# 03_-CONNECTOR_SBC.net
KiCad netlist of a schematic drawn in Altium Designer
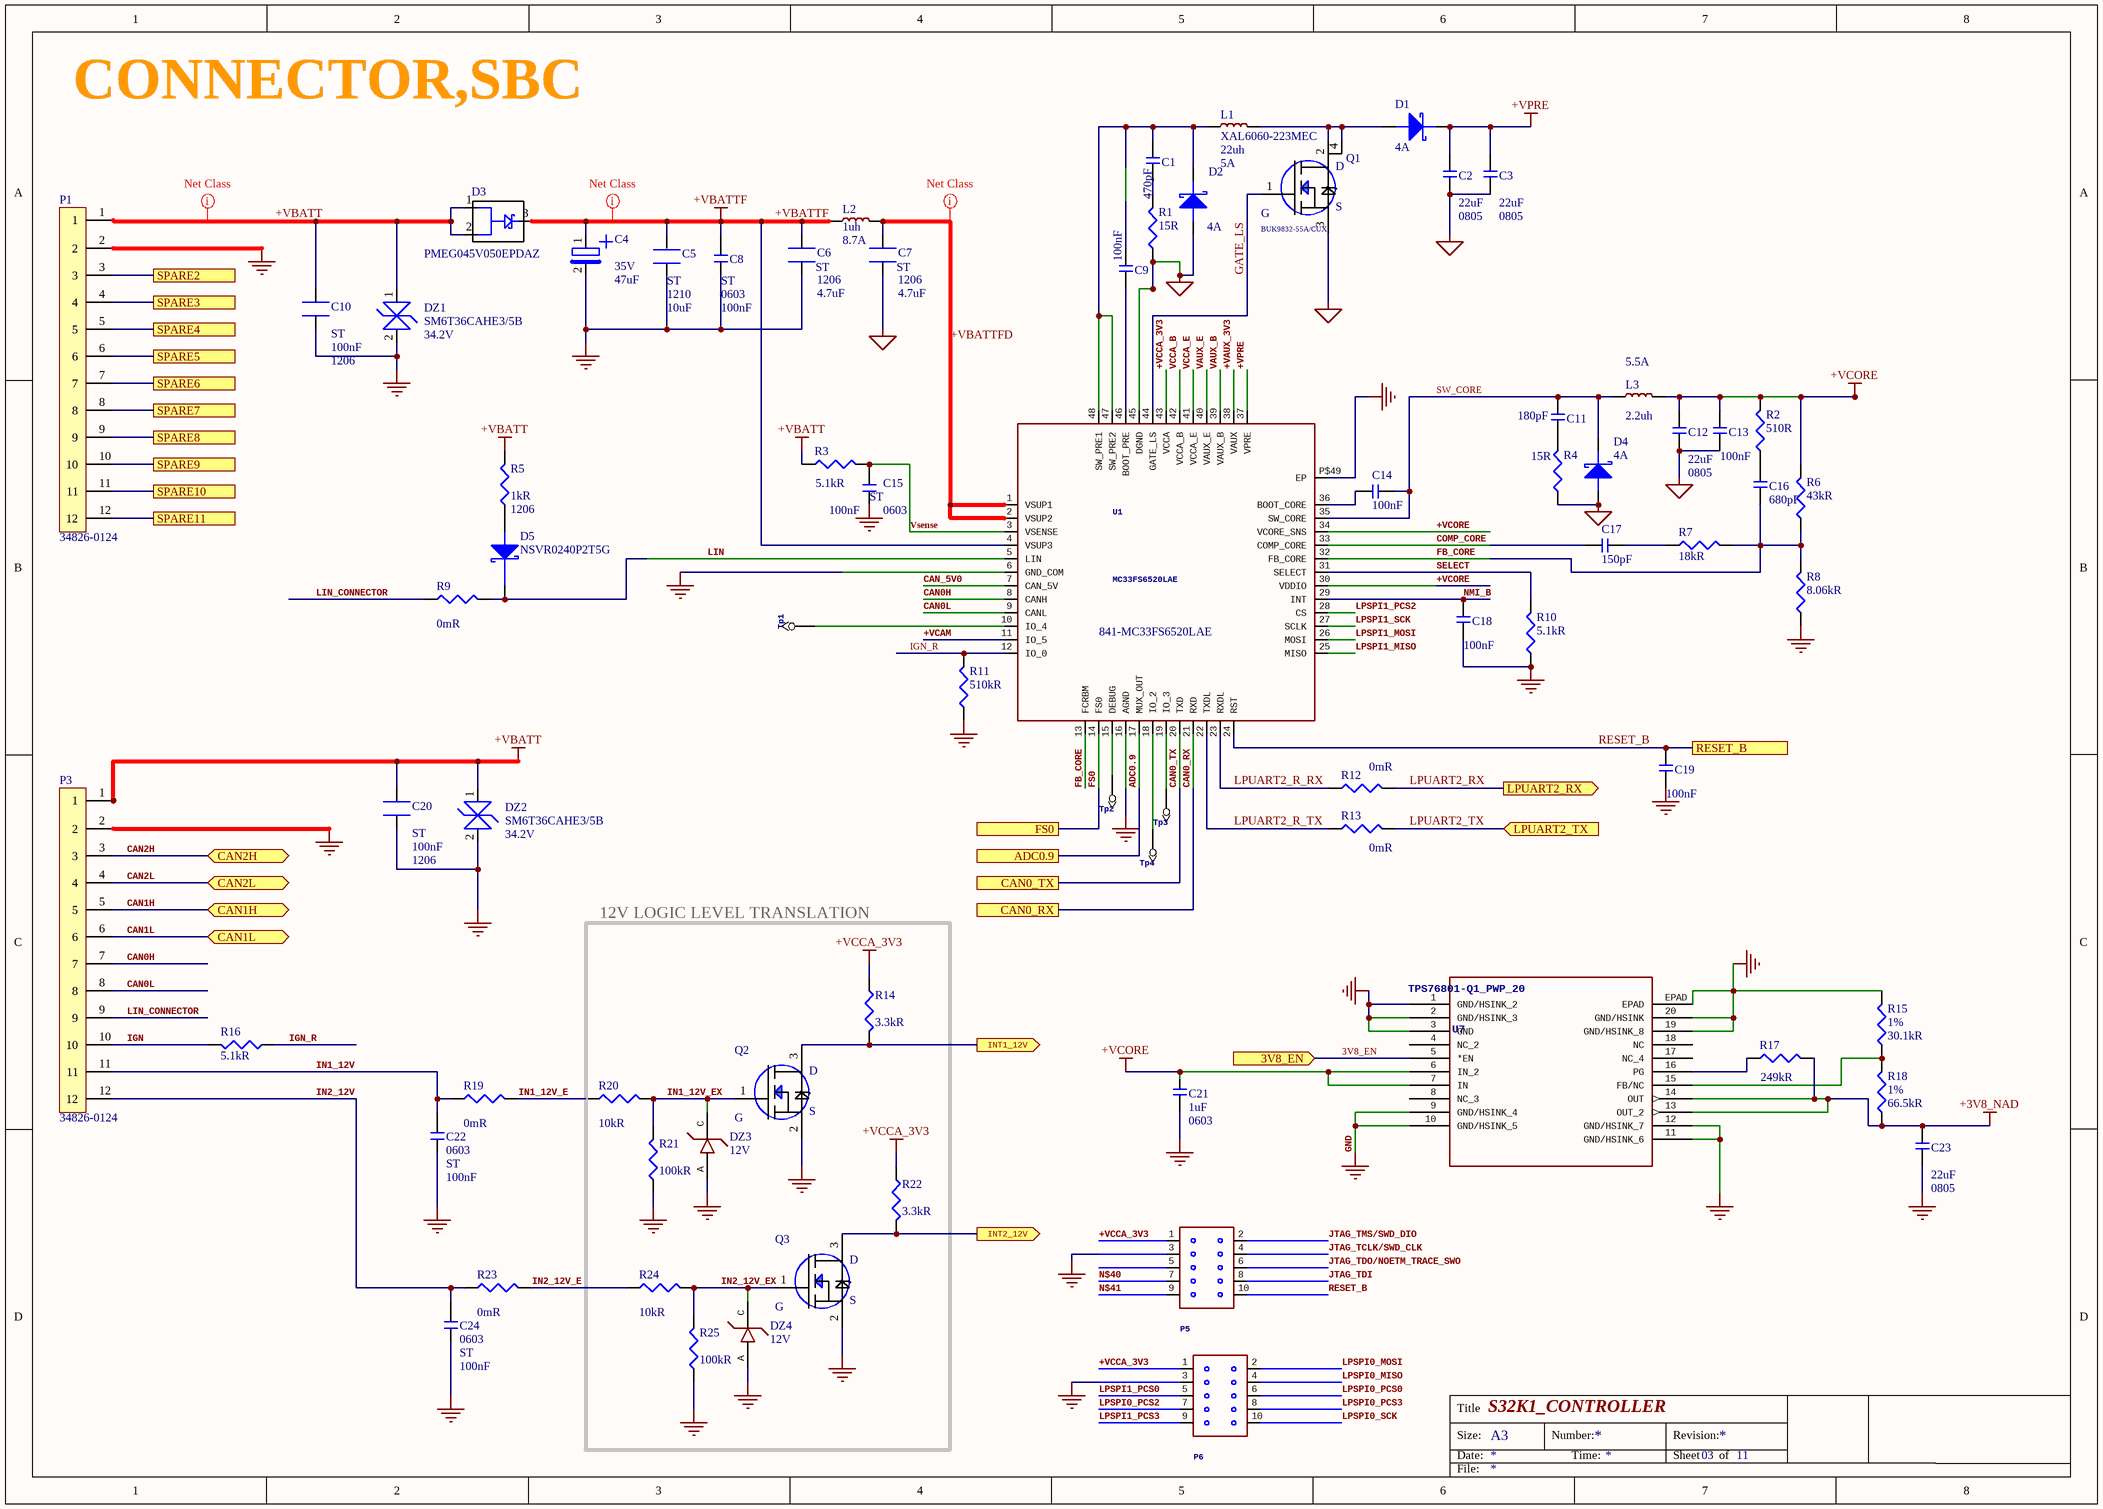
[diagram p0: [03]-CONNECTOR,SBC.SchDoc]

(export (version "E")
  (design (tool "Eeschema 10.0.6"))
  (components
    (comp (ref "C1")
      (value "C0402S471K3RACAUTO")
      (footprint "CAP0402")
      (description "Cap Ceramic 470pF 25V X7R 10% SMD 0402 125°C Paper T/R")
      (fields (field (name "MANUFACTURER") "KEMET") (field (name "PARAMETER 1") "470pF"))
      (libsource (lib "altium-import") (part "root_0_C0402S471K3RACAUTO_"))
    )
    (comp (ref "C2")
      (value "GRT21BR61E226ME13L")
      (footprint "CAP0805")
      (description "0805 22 uF 25 V ±20% Tolerance X5R Multilayer Ceramic Capacitor")
      (fields
        (field (name "MANUFACTURER") "Murata")
        (field (name "TOLERANCE") "20%")
        (field (name "CAPACITANCE") "22uF")
        (field (name "CASE/PACKAGE") "0805")
      )
      (libsource (lib "altium-import") (part "root_0_GRT21BR61E226ME13L_"))
    )
    (comp (ref "C3")
      (value "GRT21BR61E226ME13L")
      (footprint "CAP0805")
      (description "0805 22 uF 25 V ±20% Tolerance X5R Multilayer Ceramic Capacitor")
      (fields
        (field (name "MANUFACTURER") "Murata")
        (field (name "TOLERANCE") "20%")
        (field (name "CAPACITANCE") "22uF")
        (field (name "CASE/PACKAGE") "0805")
      )
      (libsource (lib "altium-import") (part "root_0_GRT21BR61E226ME13L_"))
    )
    (comp (ref "C4")
      (value "EMZA350ADA470MF61G")
      (footprint "CAPAE7263X58L")
      (description "Aluminum Electrolytic Capacitor 47UF 35V 20%, SMD, Full Reel")
      (fields
        (field (name "MANUFACTURER") "United Chemi-Con")
        (field (name "TOLERANCE") "20%")
        (field (name "VOLTAGE RATING") "35V")
        (field (name "CAPACITANCE") "47uF")
      )
      (libsource (lib "altium-import") (part "root_0_EMZA350ADA470MF61G_"))
    )
    (comp (ref "C5")
      (value "CGA6P3X7S1H106K250AE")
      (description "Cap Ceramic 10uF 50V X7S 10% Pad SMD 1210 Soft Termination 125C Automotive T/R")
      (fields
        (field (name "MANUFACTURER") "TDK")
        (field (name "TOLERANCE") "10%")
        (field (name "PARAMETER 1") "ST")
        (field (name "CASE CODE (IMPERIAL)") "1210")
        (field (name "CAPACITANCE") "10uF")
      )
      (libsource (lib "altium-import") (part "root_0_CGA6P3X7S1H106K250AE_"))
    )
    (comp (ref "C6")
      (value "CGA5L3X7R1H475K160AE")
      (footprint "CAP1206")
      (description "Cap Ceramic 4.7uF 50V X7R 10% Pad SMD 1206 Soft Termination 125C Automotive T/R")
      (fields
        (field (name "MANUFACTURER") "TDK")
        (field (name "TOLERANCE") "10%")
        (field (name "CASE CODE (IMPERIAL)") "1206")
        (field (name "CAPACITANCE") "4.7uF")
        (field (name "PARAMETER 1") "ST")
      )
      (libsource (lib "altium-import") (part "root_0_CGA5L3X7R1H475K160AE_"))
    )
    (comp (ref "C7")
      (value "CGA5L3X7R1H475K160AE")
      (footprint "CAP1206")
      (description "Cap Ceramic 4.7uF 50V X7R 10% Pad SMD 1206 Soft Termination 125C Automotive T/R")
      (fields
        (field (name "MANUFACTURER") "TDK")
        (field (name "TOLERANCE") "10%")
        (field (name "CASE CODE (IMPERIAL)") "1206")
        (field (name "CAPACITANCE") "4.7uF")
        (field (name "PARAMETER 1") "ST")
      )
      (libsource (lib "altium-import") (part "root_0_CGA5L3X7R1H475K160AE_"))
    )
    (comp (ref "C8")
      (value "06035C104K4Z2A")
      (footprint "CAP0603")
      (description "Capacitor: ceramic; MLCC; 100nF; 50V; X7R; ±10%; SMD; 0603")
      (fields
        (field (name "MANUFACTURER") "AVX")
        (field (name "TOLERANCE") "10%")
        (field (name "CASE CODE (IMPERIAL)") "0603")
        (field (name "PARAMETER 1") "ST")
        (field (name "CAPACITANCE") "100nF")
      )
      (libsource (lib "WeOnReferenceBoard") (part "06035C104K4Z2A"))
    )
    (comp (ref "C9")
      (value "GCM155R71C104KA55D")
      (footprint "CAP0402")
      (description "Multilayer Ceramic Capacitors (MLCC) - SMD/SMT 0402 0.1uF 16volts X7R 10%")
      (fields
        (field (name "MANUFACTURER") "Murata")
        (field (name "TOLERANCE") "10%")
        (field (name "CAPACITANCE") "100nF")
      )
      (libsource (lib "altium-import") (part "root_0_GCM155R71C104KA55D_"))
    )
    (comp (ref "C10")
      (value "C1206X104K2RACAUTO")
      (footprint "CAP1206")
      (description "Cap Ceramic 0.1uF 200V X7R 10% Pad SMD 1206 Flexible Termination 125C Automotive Medical T/R")
      (fields
        (field (name "MANUFACTURER") "KEMET")
        (field (name "TOLERANCE") "10%")
        (field (name "PARAMETER 1") "ST")
        (field (name "CAPACITANCE") "100nF")
        (field (name "CASE/PACKAGE") "1206")
      )
      (libsource (lib "WeOnReferenceSchlib") (part "C1206X104K2RACAUTO"))
    )
    (comp (ref "C11")
      (value "UMK105CH181JVHF")
      (footprint "CAP0402")
      (description "Cap Ceramic 180pF 50V 0402")
      (fields (field (name "MANUFACTURER") "Taiyo Yuden") (field (name "PARAMETER 1") "180pF"))
      (libsource (lib "altium-import") (part "root_0_UMK105CH181JVHF_"))
    )
    (comp (ref "C12")
      (value "GRT21BR61E226ME13L")
      (footprint "CAP0805")
      (description "0805 22 uF 25 V ±20% Tolerance X5R Multilayer Ceramic Capacitor")
      (fields
        (field (name "MANUFACTURER") "Murata")
        (field (name "TOLERANCE") "20%")
        (field (name "CAPACITANCE") "22uF")
        (field (name "CASE/PACKAGE") "0805")
      )
      (libsource (lib "altium-import") (part "root_0_GRT21BR61E226ME13L_"))
    )
    (comp (ref "C13")
      (value "GCM155R71C104KA55D")
      (footprint "CAP0402")
      (description "Multilayer Ceramic Capacitors (MLCC) - SMD/SMT 0402 0.1uF 16volts X7R 10%")
      (fields
        (field (name "MANUFACTURER") "Murata")
        (field (name "TOLERANCE") "10%")
        (field (name "CAPACITANCE") "100nF")
      )
      (libsource (lib "altium-import") (part "root_0_GCM155R71C104KA55D_"))
    )
    (comp (ref "C14")
      (value "GCM155R71C104KA55D")
      (footprint "CAP0402")
      (description "Multilayer Ceramic Capacitors (MLCC) - SMD/SMT 0402 0.1uF 16volts X7R 10%")
      (fields
        (field (name "MANUFACTURER") "Murata")
        (field (name "TOLERANCE") "10%")
        (field (name "CAPACITANCE") "100nF")
      )
      (libsource (lib "altium-import") (part "root_1_GCM155R71C104KA55D_"))
    )
    (comp (ref "C15")
      (value "06035C104K4Z2A")
      (footprint "CAP0603")
      (description "Capacitor: ceramic; MLCC; 100nF; 50V; X7R; ±10%; SMD; 0603")
      (fields
        (field (name "MANUFACTURER") "AVX")
        (field (name "TOLERANCE") "10%")
        (field (name "CASE CODE (IMPERIAL)") "0603")
        (field (name "PARAMETER 1") "ST")
        (field (name "CAPACITANCE") "100nF")
      )
      (libsource (lib "WeOnReferenceBoard") (part "06035C104K4Z2A"))
    )
    (comp (ref "C16")
      (value "C0402C681K5RACAUTO")
      (footprint "CAP0402")
      (description "Cap Ceramic 680pF 50V X7R 10% SMD 0402 125°C Punched Paper T/R")
      (fields
        (field (name "MANUFACTURER") "KEMET")
        (field (name "TOLERANCE") "10%")
        (field (name "CAPACITANCE") "680pF")
      )
      (libsource (lib "altium-import") (part "root_0_C0402C681K5RACAUTO_"))
    )
    (comp (ref "C17")
      (value "GCM1555C1H151JA16D")
      (footprint "CAP0402")
      (description "0402 150 pF 50 V ±5 % Tolerance C0G SMT Multilayer Ceramic Capacitor")
      (fields
        (field (name "MANUFACTURER") "Murata")
        (field (name "TOLERANCE") "5%")
        (field (name "CAPACITANCE") "150pF")
      )
      (libsource (lib "WeOnReferenceBoard") (part "GCM1555C1H151JA16D"))
    )
    (comp (ref "C18")
      (value "GCM155R71C104KA55D")
      (footprint "CAP0402")
      (description "Multilayer Ceramic Capacitors (MLCC) - SMD/SMT 0402 0.1uF 16volts X7R 10%")
      (fields
        (field (name "MANUFACTURER") "Murata")
        (field (name "TOLERANCE") "10%")
        (field (name "CAPACITANCE") "100nF")
      )
      (libsource (lib "altium-import") (part "root_0_GCM155R71C104KA55D_"))
    )
    (comp (ref "C19")
      (value "GCM155R71C104KA55D")
      (footprint "CAP0402")
      (description "Multilayer Ceramic Capacitors (MLCC) - SMD/SMT 0402 0.1uF 16volts X7R 10%")
      (fields
        (field (name "MANUFACTURER") "Murata")
        (field (name "TOLERANCE") "10%")
        (field (name "CAPACITANCE") "100nF")
      )
      (libsource (lib "altium-import") (part "root_0_GCM155R71C104KA55D_"))
    )
    (comp (ref "C20")
      (value "C1206X104K2RACAUTO")
      (footprint "CAP1206")
      (description "Cap Ceramic 0.1uF 200V X7R 10% Pad SMD 1206 Flexible Termination 125C Automotive Medical T/R")
      (fields
        (field (name "MANUFACTURER") "KEMET")
        (field (name "TOLERANCE") "10%")
        (field (name "PARAMETER 1") "ST")
        (field (name "CAPACITANCE") "100nF")
        (field (name "CASE/PACKAGE") "1206")
      )
      (libsource (lib "WeOnReferenceSchlib") (part "C1206X104K2RACAUTO"))
    )
    (comp (ref "C21")
      (value "CGA3E1X7R1C105K080AC")
      (footprint "CAP0603")
      (description "CGA Series 0603 1 uF 16 V ±10 % Tolerance X7R SMT Multilayer Ceramic Capacitor")
      (fields
        (field (name "MANUFACTURER") "TDK")
        (field (name "TOLERANCE") "10%")
        (field (name "CAPACITANCE") "1uF")
        (field (name "CASE/PACKAGE") "0603")
      )
      (libsource (lib "altium-import") (part "root_0_CGA3E1X7R1C105K080AC_"))
    )
    (comp (ref "C22")
      (value "06035C104K4Z2A")
      (footprint "CAP0603")
      (description "Capacitor: ceramic; MLCC; 100nF; 50V; X7R; ±10%; SMD; 0603")
      (fields
        (field (name "MANUFACTURER") "AVX")
        (field (name "TOLERANCE") "10%")
        (field (name "CASE CODE (IMPERIAL)") "0603")
        (field (name "PARAMETER 1") "ST")
        (field (name "CAPACITANCE") "100nF")
      )
      (libsource (lib "WeOnReferenceBoard") (part "06035C104K4Z2A"))
    )
    (comp (ref "C23")
      (value "GRT21BR61E226ME13L")
      (footprint "CAP0805")
      (description "0805 22 uF 25 V ±20% Tolerance X5R Multilayer Ceramic Capacitor")
      (fields
        (field (name "MANUFACTURER") "Murata")
        (field (name "TOLERANCE") "20%")
        (field (name "CAPACITANCE") "22uF")
        (field (name "CASE/PACKAGE") "0805")
      )
      (libsource (lib "altium-import") (part "root_0_GRT21BR61E226ME13L_"))
    )
    (comp (ref "C24")
      (value "06035C104K4Z2A")
      (footprint "CAP0603")
      (description "Capacitor: ceramic; MLCC; 100nF; 50V; X7R; ±10%; SMD; 0603")
      (fields
        (field (name "MANUFACTURER") "AVX")
        (field (name "TOLERANCE") "10%")
        (field (name "CASE CODE (IMPERIAL)") "0603")
        (field (name "PARAMETER 1") "ST")
        (field (name "CAPACITANCE") "100nF")
      )
      (libsource (lib "WeOnReferenceBoard") (part "06035C104K4Z2A"))
    )
    (comp (ref "D1")
      (value "SSB43LHE3_A/I")
      (footprint "DO-214AA")
      (description "Diode Schottky Rectifier 30V 4A 2-Pin DO-214AA Plastic T/R")
      (fields (field (name "MANUFACTURER") "Vishay") (field (name "AVERAGE RECTIFIED CURRENT") "4A"))
      (libsource (lib "altium-import") (part "root_0_SSB43LHE3_A/I_"))
    )
    (comp (ref "D2")
      (value "SSB43LHE3_A/I")
      (footprint "DO-214AA")
      (description "Diode Schottky Rectifier 30V 4A 2-Pin DO-214AA Plastic T/R")
      (fields (field (name "MANUFACTURER") "Vishay") (field (name "AVERAGE RECTIFIED CURRENT") "4A"))
      (libsource (lib "altium-import") (part "root_1_SSB43LHE3_A/I_"))
    )
    (comp (ref "D3")
      (value "PMEG045V050EPDAZ")
      (footprint "SOT1289")
      (description "Diode Schottky Rectifier 45V 5A 3-Pin SOT-1289 T/R")
      (fields (field (name "MANUFACTURER") "Nexperia"))
      (libsource (lib "altium-import") (part "root_2_PMEG045V050EPDAZ_"))
    )
    (comp (ref "D4")
      (value "SSB43LHE3_A/I")
      (footprint "DO-214AA")
      (description "Diode Schottky Rectifier 30V 4A 2-Pin DO-214AA Plastic T/R")
      (fields (field (name "MANUFACTURER") "Vishay") (field (name "AVERAGE RECTIFIED CURRENT") "4A"))
      (libsource (lib "altium-import") (part "root_1_SSB43LHE3_A/I_"))
    )
    (comp (ref "D5")
      (value "NSVR0240P2T5G")
      (footprint "SOD923")
      (description "Diode Schottky Barrier Diode 40V 0.2A 2-Pin SOD-923 T/R")
      (fields (field (name "MANUFACTURER") "ON Semiconductor"))
      (libsource (lib "altium-import") (part "root_3_NSVR0240P2T5G_"))
    )
    (comp (ref "DZ1")
      (value "SM6T36CAHE3/5B")
      (footprint "DO-214AA")
      (description "Diode TVS Single Bi-Dir 30.8V 600W Automotive 2-Pin SMB T/R")
      (fields (field (name "MANUFACTURER") "Vishay") (field (name "BREAKDOWN VOLTAGE") "34.2V"))
      (libsource (lib "WeOnReferenceSchlib") (part "SM6T36CAHE3/5B"))
    )
    (comp (ref "DZ2")
      (value "SM6T36CAHE3/5B")
      (footprint "DO-214AA")
      (description "Diode TVS Single Bi-Dir 30.8V 600W Automotive 2-Pin SMB T/R")
      (fields (field (name "MANUFACTURER") "Vishay") (field (name "BREAKDOWN VOLTAGE") "34.2V"))
      (libsource (lib "WeOnReferenceSchlib") (part "SM6T36CAHE3/5B"))
    )
    (comp (ref "DZ3")
      (value "SZMMBZ5242BL**G")
      (footprint "MINI50_TO236")
      (fields
        (field (name "MANUFACTURER") "ON Semiconductor")
        (field (name "MANUFACTURER PART NUMBER") "SZMMBZ5242BLT1G")
        (field (name "TOLERANCE") "5%")
        (field (name "ZENER VOLTAGE") "12V")
      )
      (libsource (lib "WeOnReferenceBoard") (part "SZMMBZ5242BL**G"))
    )
    (comp (ref "DZ4")
      (value "SZMMBZ5242BL**G")
      (footprint "MINI50_TO236")
      (fields
        (field (name "MANUFACTURER") "ON Semiconductor")
        (field (name "MANUFACTURER PART NUMBER") "SZMMBZ5242BLT1G")
        (field (name "TOLERANCE") "5%")
        (field (name "ZENER VOLTAGE") "12V")
      )
      (libsource (lib "WeOnReferenceBoard") (part "SZMMBZ5242BL**G"))
    )
    (comp (ref "L1")
      (value "XAL6060-223MEC")
      (footprint "INDP6666X61L")
      (description "Power inductor, shielded, 20% tol, SMT, RoHS, halogen f")
      (fields
        (field (name "MANUFACTURER") "Coilcraft")
        (field (name "TOLERANCE") "20%")
        (field (name "INDUCTANCE") "22uh")
        (field (name "MAX DC CURRENT") "5A")
      )
      (libsource (lib "WeOnReferenceBoard") (part "XAL6060-223MEC"))
    )
    (comp (ref "L2")
      (value "XAL4020-102MEB")
      (footprint "INDC4040X21L")
      (description "Power inductor, shielded, 20% tol, SMT, RoHS, halogen f")
      (fields
        (field (name "MANUFACTURER") "Coilcraft")
        (field (name "TOLERANCE") "20%")
        (field (name "INDUCTANCE") "1uh")
        (field (name "SATURATION CURRENT") "8.7A")
      )
      (libsource (lib "WeOnReferenceBoard") (part "XAL4020-102MEB"))
    )
    (comp (ref "L3")
      (value "XAL4020-222MEB")
      (footprint "XAL4020")
      (description "Power inductor, shielded, 20% tol, SMT, RoHS, halogen f")
      (fields
        (field (name "MANUFACTURER") "Coilcraft")
        (field (name "TOLERANCE") "20%")
        (field (name "INDUCTANCE") "2.2uh")
        (field (name "MAX DC CURRENT") "5.5A")
      )
      (libsource (lib "altium-import") (part "root_0_XAL4020-222MEB_"))
    )
    (comp (ref "P1")
      (value "34826-0124")
      (description "Mini50™ Unsealed, Dual Row, Right-Angle Header, 12 Circuit, Polarization Option A, Black, Tray")
      (fields (field (name "MANUFACTURER") "Molex"))
      (libsource (lib "WeOnReferenceBoard") (part "34826-0124"))
    )
    (comp (ref "P3")
      (value "34826-0124")
      (description "Mini50™ Unsealed, Dual Row, Right-Angle Header, 12 Circuit, Polarization Option A, Black, Tray")
      (fields (field (name "MANUFACTURER") "Molex"))
      (libsource (lib "WeOnReferenceBoard") (part "34826-0124"))
    )
    (comp (ref "P5")
      (value "FTSH105-05")
      (footprint "WEONREFERENCEPLATFORM_FTSH105-05")
      (libsource (lib "WeOnReferenceBoard") (part "FTSH105-05"))
    )
    (comp (ref "P6")
      (value "FTSH105-05")
      (footprint "WEONREFERENCEPLATFORM_FTSH105-05")
      (libsource (lib "WeOnReferenceBoard") (part "FTSH105-05"))
    )
    (comp (ref "Q1")
      (value "BUK9832-55A/CUX")
      (footprint "SOT230P700X180-4L")
      (description "BUK9832 Series 55 V 32 mOhm N-Channel TrenchMOS Logic Level FET - SOT-223")
      (fields
        (field (name "MANUFACTURER") "Nexperia")
        (field (name "MANUFACTURER PART NUMBER") "BUK9832-55A/CUX")
      )
      (libsource (lib "altium-import") (part "root_0_BUK9832-55A/CUX_"))
    )
    (comp (ref "Q2")
      (value "BSS138BKW,115")
      (footprint "SOT323_bss138bkw")
      (description "BSS138BKW - 60 V, 320 mA N-channel Trench MOSFET")
      (fields (field (name "MANUFACTURER") "Nexperia"))
      (libsource (lib "WeOnReferenceBoard") (part "BSS138BKW,115"))
    )
    (comp (ref "Q3")
      (value "BSS138BKW,115")
      (footprint "SOT323_bss138bkw")
      (description "BSS138BKW - 60 V, 320 mA N-channel Trench MOSFET")
      (fields (field (name "MANUFACTURER") "Nexperia"))
      (libsource (lib "WeOnReferenceBoard") (part "BSS138BKW,115"))
    )
    (comp (ref "R1")
      (value "ERJ-2GEJ150X")
      (footprint "RES0402")
      (description "Res Thick Film 0402 15 Ohm 5% 1/10W ±200ppm/°C Molded SMD SMD Punched Carrier T/R")
      (fields
        (field (name "MANUFACTURER") "Panasonic")
        (field (name "RESISTANCE") "15R")
        (field (name "TOLERANCE") "5%")
      )
      (libsource (lib "altium-import") (part "root_1_ERJ-2GEJ150X_"))
    )
    (comp (ref "R2")
      (value "RK73B1ETTP511J")
      (footprint "RES0402")
      (description "Res Thick Film 0402 510 Ohm 5% 0.1W(1/10W) ±200ppm/C Pad SMD Automotive T/R")
      (fields
        (field (name "MANUFACTURER") "KOA Speer")
        (field (name "TOLERANCE") "5%")
        (field (name "RESISTANCE") "510R")
      )
      (libsource (lib "altium-import") (part "root_1_RK73B1ETTP511J_"))
    )
    (comp (ref "R3")
      (value "ERJ-2GEJ512X")
      (footprint "RES0402")
      (description "Res Thick Film 0402 5.1K Ohm 5% 1/10W ±200ppm/°C Molded SMD SMD Punched Carrier T/R")
      (fields
        (field (name "MANUFACTURER") "Panasonic")
        (field (name "TOLERANCE") "5%")
        (field (name "RESISTANCE") "5.1kR")
      )
      (libsource (lib "altium-import") (part "root_0_ERJ-2GEJ512X_"))
    )
    (comp (ref "R4")
      (value "ERJ-2GEJ150X")
      (footprint "RES0402")
      (description "Res Thick Film 0402 15 Ohm 5% 1/10W ±200ppm/°C Molded SMD SMD Punched Carrier T/R")
      (fields
        (field (name "MANUFACTURER") "Panasonic")
        (field (name "RESISTANCE") "15R")
        (field (name "TOLERANCE") "5%")
      )
      (libsource (lib "altium-import") (part "root_1_ERJ-2GEJ150X_"))
    )
    (comp (ref "R5")
      (value "ERJ-8GEYJ102V")
      (footprint "RES1206")
      (description "Res Thick Film 1206 1K Ohm 5% 1/4W ±200ppm/°C Molded SMD Punched Carrier T/R")
      (fields
        (field (name "MANUFACTURER") "Panasonic")
        (field (name "TOLERANCE") "5%")
        (field (name "RESISTANCE") "1kR")
        (field (name "CASE/PACKAGE") "1206")
      )
      (libsource (lib "WeOnReferenceBoard") (part "ERJ-8GEYJ102V"))
    )
    (comp (ref "R6")
      (value "RK73H1ETTP4302F")
      (footprint "RES0402")
      (description "Res Thick Film 0402 43K Ohm 1% 0.1W(1/10W) ±100ppm/C Pad SMD Automotive T/R")
      (fields
        (field (name "MANUFACTURER") "KOA Speer")
        (field (name "TOLERANCE") "1%")
        (field (name "RESISTANCE") "43kR")
      )
      (libsource (lib "altium-import") (part "root_1_RK73H1ETTP4302F_"))
    )
    (comp (ref "R7")
      (value "RK73B1ETTP183J")
      (footprint "RES0402")
      (description "Res Thick Film 0402 18K Ohm 5% 0.1W(1/10W) ±200ppm/C Pad SMD Automotive T/R")
      (fields
        (field (name "MANUFACTURER") "KOA Speer")
        (field (name "TOLERANCE") "5%")
        (field (name "RESISTANCE") "18kR")
      )
      (libsource (lib "altium-import") (part "root_0_RK73B1ETTP183J_"))
    )
    (comp (ref "R8")
      (value "RK73H1ETTP8061F")
      (footprint "RES0402")
      (description "Res Thick Film 0402 8.06K Ohm 1% 0.1W(1/10W) ±100ppm/C Pad SMD Automotive T/R")
      (fields
        (field (name "MANUFACTURER") "KOA Speer")
        (field (name "TOLERANCE") "1%")
        (field (name "RESISTANCE") "8.06kR")
      )
      (libsource (lib "altium-import") (part "root_1_RK73H1ETTP8061F_"))
    )
    (comp (ref "R9")
      (value "ERJ-2GE0R00X")
      (footprint "RES0402")
      (description "ERJ Series 0402 0 Ohm 0.1 W Jumper Surface Mount Thick Film Chip Resistor")
      (fields
        (field (name "MANUFACTURER") "Panasonic")
        (field (name "TOLERANCE") "5%")
        (field (name "RESISTANCE") "0mR")
      )
      (libsource (lib "WeOnReferenceBoard") (part "ERJ-2GE0R00X"))
    )
    (comp (ref "R10")
      (value "RK73B1ETTP512J")
      (footprint "RES0402")
      (description "Res Thick Film 0402 5.1K Ohm 5% 0.1W(1/10W) ±200ppm/C Pad SMD Automotive T/R")
      (fields
        (field (name "MANUFACTURER") "KOA Speer")
        (field (name "TOLERANCE") "5%")
        (field (name "RESISTANCE") "5.1kR")
      )
      (libsource (lib "altium-import") (part "root_1_RK73B1ETTP512J_"))
    )
    (comp (ref "R11")
      (value "RK73B1ETTP514J")
      (footprint "RES0402")
      (description "Res Thick Film 0402 510K Ohm 5% 0.1W(1/10W) ±200ppm/C Pad SMD Automotive T/R")
      (fields
        (field (name "MANUFACTURER") "KOA Speer")
        (field (name "TOLERANCE") "5%")
        (field (name "RESISTANCE") "510kR")
      )
      (libsource (lib "altium-import") (part "root_1_RK73B1ETTP514J_"))
    )
    (comp (ref "R12")
      (value "ERJ-2GE0R00X")
      (footprint "RES0402")
      (description "ERJ Series 0402 0 Ohm 0.1 W Jumper Surface Mount Thick Film Chip Resistor")
      (fields
        (field (name "MANUFACTURER") "Panasonic")
        (field (name "TOLERANCE") "5%")
        (field (name "RESISTANCE") "0mR")
      )
      (libsource (lib "WeOnReferenceBoard") (part "ERJ-2GE0R00X"))
    )
    (comp (ref "R13")
      (value "ERJ-2GE0R00X")
      (footprint "RES0402")
      (description "ERJ Series 0402 0 Ohm 0.1 W Jumper Surface Mount Thick Film Chip Resistor")
      (fields
        (field (name "MANUFACTURER") "Panasonic")
        (field (name "TOLERANCE") "5%")
        (field (name "RESISTANCE") "0mR")
      )
      (libsource (lib "WeOnReferenceBoard") (part "ERJ-2GE0R00X"))
    )
    (comp (ref "R14")
      (value "ERJ-2GEJ332X")
      (footprint "RES0402")
      (description "Res Thick Film 0402 3.3K Ohm 5% 1/10W ±200ppm/°C Molded SMD SMD Punched Carrier T/R")
      (fields
        (field (name "MANUFACTURER") "Panasonic")
        (field (name "TOLERANCE") "5%")
        (field (name "RESISTANCE") "3.3kR")
      )
      (libsource (lib "WeOnReferenceBoard") (part "ERJ-2GEJ332X"))
    )
    (comp (ref "R15")
      (value "RK73H1ETTP3012F")
      (footprint "RES0402")
      (description "Res Thick Film 0402 30.1K Ohm 1% 0.1W(1/10W) ±100ppm/C Pad SMD Automotive T/R")
      (fields
        (field (name "MANUFACTURER") "KOA Speer")
        (field (name "TOLERANCE") "1%")
        (field (name "RESISTANCE") "30.1kR")
      )
      (libsource (lib "altium-import") (part "root_1_RK73H1ETTP3012F_"))
    )
    (comp (ref "R16")
      (value "RK73B1ETTP512J")
      (footprint "RES0402")
      (description "Res Thick Film 0402 5.1K Ohm 5% 0.1W(1/10W) ±200ppm/C Pad SMD Automotive T/R")
      (fields
        (field (name "MANUFACTURER") "KOA Speer")
        (field (name "TOLERANCE") "5%")
        (field (name "RESISTANCE") "5.1kR")
      )
      (libsource (lib "altium-import") (part "root_2_RK73B1ETTP512J_"))
    )
    (comp (ref "R17")
      (value "RK73H1ETTP2493F")
      (footprint "RES0402")
      (description "Res Thick Film 0402 249K Ohm 1% 0.1W(1/10W) ±100ppm/C Pad SMD Automotive T/R")
      (fields
        (field (name "MANUFACTURER") "KOA Speer")
        (field (name "TOLERANCE") "1%")
        (field (name "RESISTANCE") "249kR")
      )
      (libsource (lib "altium-import") (part "root_0_RK73H1ETTP2493F_"))
    )
    (comp (ref "R18")
      (value "RK73H1ETTP6652F")
      (description "Res Thick Film 0402 66.5K Ohm 1% 0.1W(1/10W) ±100ppm/C Pad SMD Automotive T/R")
      (fields
        (field (name "MANUFACTURER") "KOA Speer")
        (field (name "TOLERANCE") "1%")
        (field (name "RESISTANCE") "66.5kR")
      )
      (libsource (lib "altium-import") (part "root_1_RK73H1ETTP6652F_"))
    )
    (comp (ref "R19")
      (value "ERJ-2GE0R00X")
      (footprint "RES0402")
      (description "ERJ Series 0402 0 Ohm 0.1 W Jumper Surface Mount Thick Film Chip Resistor")
      (fields
        (field (name "MANUFACTURER") "Panasonic")
        (field (name "TOLERANCE") "5%")
        (field (name "RESISTANCE") "0mR")
      )
      (libsource (lib "WeOnReferenceBoard") (part "ERJ-2GE0R00X"))
    )
    (comp (ref "R20")
      (value "ERJ-2GEJ103X")
      (footprint "RES0402")
      (description "Res Thick Film 0402 10K Ohm 5% 1/10W ±200ppm/°C Molded SMD SMD Punched Carrier T/R")
      (fields
        (field (name "MANUFACTURER") "Panasonic")
        (field (name "TOLERANCE") "5%")
        (field (name "RESISTANCE") "10kR")
      )
      (libsource (lib "WeOnReferenceBoard") (part "ERJ-2GEJ103X"))
    )
    (comp (ref "R21")
      (value "ERJ-2GEJ104X")
      (footprint "RES0402")
      (description "Res Thick Film 0402 100K Ohm 5% 1/10W ±200ppm/°C Molded SMD SMD Punched Carrier T/R")
      (fields
        (field (name "MANUFACTURER") "Panasonic")
        (field (name "TOLERANCE") "5%")
        (field (name "RESISTANCE") "100kR")
      )
      (libsource (lib "WeOnReferenceBoard") (part "ERJ-2GEJ104X"))
    )
    (comp (ref "R22")
      (value "ERJ-2GEJ332X")
      (footprint "RES0402")
      (description "Res Thick Film 0402 3.3K Ohm 5% 1/10W ±200ppm/°C Molded SMD SMD Punched Carrier T/R")
      (fields
        (field (name "MANUFACTURER") "Panasonic")
        (field (name "TOLERANCE") "5%")
        (field (name "RESISTANCE") "3.3kR")
      )
      (libsource (lib "WeOnReferenceBoard") (part "ERJ-2GEJ332X"))
    )
    (comp (ref "R23")
      (value "ERJ-2GE0R00X")
      (footprint "RES0402")
      (description "ERJ Series 0402 0 Ohm 0.1 W Jumper Surface Mount Thick Film Chip Resistor")
      (fields
        (field (name "MANUFACTURER") "Panasonic")
        (field (name "TOLERANCE") "5%")
        (field (name "RESISTANCE") "0mR")
      )
      (libsource (lib "WeOnReferenceBoard") (part "ERJ-2GE0R00X"))
    )
    (comp (ref "R24")
      (value "ERJ-2GEJ103X")
      (footprint "RES0402")
      (description "Res Thick Film 0402 10K Ohm 5% 1/10W ±200ppm/°C Molded SMD SMD Punched Carrier T/R")
      (fields
        (field (name "MANUFACTURER") "Panasonic")
        (field (name "TOLERANCE") "5%")
        (field (name "RESISTANCE") "10kR")
      )
      (libsource (lib "WeOnReferenceBoard") (part "ERJ-2GEJ103X"))
    )
    (comp (ref "R25")
      (value "ERJ-2GEJ104X")
      (footprint "RES0402")
      (description "Res Thick Film 0402 100K Ohm 5% 1/10W ±200ppm/°C Molded SMD SMD Punched Carrier T/R")
      (fields
        (field (name "MANUFACTURER") "Panasonic")
        (field (name "TOLERANCE") "5%")
        (field (name "RESISTANCE") "100kR")
      )
      (libsource (lib "WeOnReferenceBoard") (part "ERJ-2GEJ104X"))
    )
    (comp (ref "Tp1")
      (value "TP")
      (footprint "TestPoint")
      (libsource (lib "altium-import") (part "root_2_TP_"))
    )
    (comp (ref "Tp2")
      (value "TP")
      (footprint "TestPoint")
      (libsource (lib "altium-import") (part "root_3_TP_"))
    )
    (comp (ref "Tp3")
      (value "TP")
      (footprint "TestPoint")
      (libsource (lib "altium-import") (part "root_3_TP_"))
    )
    (comp (ref "Tp4")
      (value "TP")
      (footprint "TestPoint")
      (libsource (lib "altium-import") (part "root_3_TP_"))
    )
    (comp (ref "U1")
      (value "MC33FS6520LAE")
      (footprint "WEONREFERENCEPLATFORM_LQFP48_7X7")
      (fields
        (field (name "MANUFACTURER") "NXP Semiconductors")
        (field (name "SUPPLIER PART NUMBER 1") "841-MC33FS6520LAE")
      )
      (libsource (lib "WeOnReferenceBoard") (part "MC33FS6520LAE"))
    )
    (comp (ref "U7")
      (value "TPS76801-Q1_PWP_20")
      (footprint "WEONREFERENCEPLATFORM_PWP20_3P38X2P4")
      (fields
        (field (name "GENERIC_PART_NUMBER") "TPS76801Q1")
        (field (name "MANUFACTURER") "Texas Instruments")
        (field (name "MANUFACTURER_PART_NUMBER") "tps76801q1_pwp_20")
      )
      (libsource (lib "WeOnReferenceBoard") (part "TPS76801-Q1_PWP_20"))
    )
  )
  (nets
    (net (code "1") (name "+3V8_NAD") (class "Default")
      (node (ref "C23") (pin "1") (pinfunction "1_1") (pintype "passive"))
      (node (ref "R17") (pin "2") (pinfunction "2_2") (pintype "passive"))
      (node (ref "R18") (pin "1") (pinfunction "1_1") (pintype "passive"))
      (node (ref "U7") (pin "13") (pinfunction "OUT_2_13") (pintype "output"))
      (node (ref "U7") (pin "14") (pinfunction "OUT_14") (pintype "output"))
    )
    (net (code "2") (name "+VBATT") (class "Default")
      (node (ref "C10") (pin "1") (pinfunction "1_1") (pintype "passive"))
      (node (ref "C20") (pin "1") (pinfunction "1_1") (pintype "passive"))
      (node (ref "D3") (pin "1") (pinfunction "A_1") (pintype "passive"))
      (node (ref "D3") (pin "2") (pinfunction "A_2") (pintype "passive"))
      (node (ref "DZ1") (pin "1") (pinfunction "1_1") (pintype "passive"))
      (node (ref "DZ2") (pin "1") (pinfunction "1_1") (pintype "passive"))
      (node (ref "P1") (pin "1") (pinfunction "1_1") (pintype "passive"))
      (node (ref "P3") (pin "1") (pinfunction "1_1") (pintype "passive"))
      (node (ref "R3") (pin "1") (pinfunction "1_1") (pintype "passive"))
      (node (ref "R5") (pin "2") (pinfunction "2_2") (pintype "passive"))
    )
    (net (code "3") (name "+VBATTF") (class "Default")
      (node (ref "C4") (pin "1") (pinfunction "1_1") (pintype "passive"))
      (node (ref "C5") (pin "1") (pinfunction "1_1") (pintype "passive"))
      (node (ref "C6") (pin "1") (pinfunction "1_1") (pintype "passive"))
      (node (ref "C8") (pin "1") (pinfunction "1_1") (pintype "passive"))
      (node (ref "D3") (pin "3") (pinfunction "K_3") (pintype "passive"))
      (node (ref "L2") (pin "1") (pinfunction "1_1") (pintype "passive"))
      (node (ref "U1") (pin "4") (pinfunction "VSUP3_4") (pintype "passive"))
    )
    (net (code "4") (name "+VCCA_3V3") (class "Default")
      (node (ref "P5") (pin "1") (pinfunction "1_1") (pintype "passive"))
      (node (ref "P6") (pin "1") (pinfunction "1_1") (pintype "passive"))
      (node (ref "R14") (pin "1") (pinfunction "1_1") (pintype "passive"))
      (node (ref "R22") (pin "1") (pinfunction "1_1") (pintype "passive"))
      (node (ref "U1") (pin "43") (pinfunction "VCCA_43") (pintype "passive"))
    )
    (net (code "5") (name "+VCORE") (class "Default")
      (node (ref "C12") (pin "1") (pinfunction "1_1") (pintype "passive"))
      (node (ref "C13") (pin "1") (pinfunction "1_1") (pintype "passive"))
      (node (ref "C21") (pin "1") (pinfunction "1_1") (pintype "passive"))
      (node (ref "L3") (pin "2") (pinfunction "2_2") (pintype "passive"))
      (node (ref "R2") (pin "2") (pinfunction "2_2") (pintype "passive"))
      (node (ref "R6") (pin "2") (pinfunction "2_2") (pintype "passive"))
      (node (ref "U1") (pin "30") (pinfunction "VDDIO_30") (pintype "passive"))
      (node (ref "U1") (pin "34") (pinfunction "VCORE_SNS_34") (pintype "passive"))
      (node (ref "U7") (pin "6") (pinfunction "IN_2_6") (pintype "passive"))
      (node (ref "U7") (pin "7") (pinfunction "IN_7") (pintype "passive"))
    )
    (net (code "6") (name "+VPRE") (class "Default")
      (node (ref "C2") (pin "1") (pinfunction "1_1") (pintype "passive"))
      (node (ref "C3") (pin "1") (pinfunction "1_1") (pintype "passive"))
      (node (ref "D1") (pin "1") (pinfunction "Cathode_1") (pintype "passive"))
      (node (ref "U1") (pin "37") (pinfunction "VPRE_37") (pintype "passive"))
    )
    (net (code "7") (name "/+VAUX_3V3") (class "Default")
      (node (ref "U1") (pin "38") (pinfunction "VAUX_38") (pintype "passive"))
    )
    (net (code "8") (name "/+VBATTFD") (class "Default")
      (node (ref "C7") (pin "1") (pinfunction "1_1") (pintype "passive"))
      (node (ref "L2") (pin "2") (pinfunction "2_2") (pintype "passive"))
      (node (ref "U1") (pin "1") (pinfunction "VSUP1_1") (pintype "passive"))
      (node (ref "U1") (pin "2") (pinfunction "VSUP2_2") (pintype "passive"))
    )
    (net (code "9") (name "/+VCAM") (class "Default")
      (node (ref "U1") (pin "11") (pinfunction "IO_5_11") (pintype "passive"))
    )
    (net (code "10") (name "/3V8_EN") (class "Default")
      (node (ref "U7") (pin "5") (pinfunction "*EN_5") (pintype "passive"))
    )
    (net (code "11") (name "/ADC0.9") (class "Default")
      (node (ref "U1") (pin "17") (pinfunction "MUX_OUT_17") (pintype "passive"))
    )
    (net (code "12") (name "/CAN0H") (class "Default")
      (node (ref "P3") (pin "7") (pinfunction "7_7") (pintype "passive"))
      (node (ref "U1") (pin "8") (pinfunction "CANH_8") (pintype "passive"))
    )
    (net (code "13") (name "/CAN0L") (class "Default")
      (node (ref "P3") (pin "8") (pinfunction "8_8") (pintype "passive"))
      (node (ref "U1") (pin "9") (pinfunction "CANL_9") (pintype "passive"))
    )
    (net (code "14") (name "/CAN0_RX") (class "Default")
      (node (ref "U1") (pin "21") (pinfunction "RXD_21") (pintype "passive"))
    )
    (net (code "15") (name "/CAN0_TX") (class "Default")
      (node (ref "U1") (pin "20") (pinfunction "TXD_20") (pintype "passive"))
    )
    (net (code "16") (name "/CAN1H") (class "Default")
      (node (ref "P3") (pin "5") (pinfunction "5_5") (pintype "passive"))
    )
    (net (code "17") (name "/CAN1L") (class "Default")
      (node (ref "P3") (pin "6") (pinfunction "6_6") (pintype "passive"))
    )
    (net (code "18") (name "/CAN2H") (class "Default")
      (node (ref "P3") (pin "3") (pinfunction "3_3") (pintype "passive"))
    )
    (net (code "19") (name "/CAN2L") (class "Default")
      (node (ref "P3") (pin "4") (pinfunction "4_4") (pintype "passive"))
    )
    (net (code "20") (name "/CAN_5V0") (class "Default")
      (node (ref "U1") (pin "7") (pinfunction "CAN_5V_7") (pintype "passive"))
    )
    (net (code "21") (name "/COMP_CORE") (class "Default")
      (node (ref "C17") (pin "1") (pinfunction "1_1") (pintype "passive"))
      (node (ref "U1") (pin "33") (pinfunction "COMP_CORE_33") (pintype "passive"))
    )
    (net (code "22") (name "/FB_CORE") (class "Default")
      (node (ref "C16") (pin "2") (pinfunction "2_2") (pintype "passive"))
      (node (ref "R6") (pin "1") (pinfunction "1_1") (pintype "passive"))
      (node (ref "R7") (pin "2") (pinfunction "2_2") (pintype "passive"))
      (node (ref "R8") (pin "2") (pinfunction "2_2") (pintype "passive"))
      (node (ref "U1") (pin "13") (pinfunction "FCRBM_13") (pintype "passive"))
      (node (ref "U1") (pin "32") (pinfunction "FB_CORE_32") (pintype "passive"))
    )
    (net (code "23") (name "/FS0") (class "Default")
      (node (ref "U1") (pin "14") (pinfunction "FS0_14") (pintype "passive"))
    )
    (net (code "24") (name "/GATE_LS") (class "Default")
      (node (ref "Q1") (pin "1") (pinfunction "G_1") (pintype "passive"))
      (node (ref "U1") (pin "44") (pinfunction "GATE_LS_44") (pintype "passive"))
    )
    (net (code "25") (name "/IGN") (class "Default")
      (node (ref "P3") (pin "10") (pinfunction "10_10") (pintype "passive"))
      (node (ref "R16") (pin "2") (pinfunction "2_2") (pintype "passive"))
    )
    (net (code "26") (name "/IGN_R") (class "Default")
      (node (ref "R11") (pin "2") (pinfunction "2_2") (pintype "passive"))
      (node (ref "R16") (pin "1") (pinfunction "1_1") (pintype "passive"))
      (node (ref "U1") (pin "12") (pinfunction "IO_0_12") (pintype "passive"))
    )
    (net (code "27") (name "/IN1_12V") (class "Default")
      (node (ref "C22") (pin "1") (pinfunction "1_1") (pintype "passive"))
      (node (ref "P3") (pin "11") (pinfunction "11_11") (pintype "passive"))
      (node (ref "R19") (pin "1") (pinfunction "1_1") (pintype "passive"))
    )
    (net (code "28") (name "/IN1_12V_E") (class "Default")
      (node (ref "R19") (pin "2") (pinfunction "2_2") (pintype "passive"))
      (node (ref "R20") (pin "1") (pinfunction "1_1") (pintype "passive"))
    )
    (net (code "29") (name "/IN1_12V_EX") (class "Default")
      (node (ref "DZ3") (pin "C") (pinfunction "3_C") (pintype "passive"))
      (node (ref "Q2") (pin "1") (pinfunction "G_1") (pintype "passive"))
      (node (ref "R20") (pin "2") (pinfunction "2_2") (pintype "passive"))
      (node (ref "R21") (pin "2") (pinfunction "2_2") (pintype "passive"))
    )
    (net (code "30") (name "/IN2_12V") (class "Default")
      (node (ref "C24") (pin "1") (pinfunction "1_1") (pintype "passive"))
      (node (ref "P3") (pin "12") (pinfunction "12_12") (pintype "passive"))
      (node (ref "R23") (pin "1") (pinfunction "1_1") (pintype "passive"))
    )
    (net (code "31") (name "/IN2_12V_E") (class "Default")
      (node (ref "R23") (pin "2") (pinfunction "2_2") (pintype "passive"))
      (node (ref "R24") (pin "1") (pinfunction "1_1") (pintype "passive"))
    )
    (net (code "32") (name "/IN2_12V_EX") (class "Default")
      (node (ref "DZ4") (pin "C") (pinfunction "3_C") (pintype "passive"))
      (node (ref "Q3") (pin "1") (pinfunction "G_1") (pintype "passive"))
      (node (ref "R24") (pin "2") (pinfunction "2_2") (pintype "passive"))
      (node (ref "R25") (pin "2") (pinfunction "2_2") (pintype "passive"))
    )
    (net (code "33") (name "/INT1_12V") (class "Default")
      (node (ref "Q2") (pin "3") (pinfunction "D_3") (pintype "passive"))
      (node (ref "R14") (pin "2") (pinfunction "2_2") (pintype "passive"))
    )
    (net (code "34") (name "/INT2_12V") (class "Default")
      (node (ref "Q3") (pin "3") (pinfunction "D_3") (pintype "passive"))
      (node (ref "R22") (pin "2") (pinfunction "2_2") (pintype "passive"))
    )
    (net (code "35") (name "/JTAG_TCLK{slash}SWD_CLK") (class "Default")
      (node (ref "P5") (pin "4") (pinfunction "4_4") (pintype "passive"))
    )
    (net (code "36") (name "/JTAG_TDI") (class "Default")
      (node (ref "P5") (pin "8") (pinfunction "8_8") (pintype "passive"))
    )
    (net (code "37") (name "/JTAG_TDO{slash}NOETM_TRACE_SWO") (class "Default")
      (node (ref "P5") (pin "6") (pinfunction "6_6") (pintype "passive"))
    )
    (net (code "38") (name "/JTAG_TMS{slash}SWD_DIO") (class "Default")
      (node (ref "P5") (pin "2") (pinfunction "2_2") (pintype "passive"))
    )
    (net (code "39") (name "/LIN") (class "Default")
      (node (ref "D5") (pin "1") (pinfunction "Cathode_1") (pintype "passive"))
      (node (ref "R9") (pin "2") (pinfunction "2_2") (pintype "passive"))
      (node (ref "U1") (pin "5") (pinfunction "LIN_5") (pintype "passive"))
    )
    (net (code "40") (name "/LIN_CONNECTOR") (class "Default")
      (node (ref "P3") (pin "9") (pinfunction "9_9") (pintype "passive"))
      (node (ref "R9") (pin "1") (pinfunction "1_1") (pintype "passive"))
    )
    (net (code "41") (name "/LPSPI0_MISO") (class "Default")
      (node (ref "P6") (pin "4") (pinfunction "4_4") (pintype "passive"))
    )
    (net (code "42") (name "/LPSPI0_MOSI") (class "Default")
      (node (ref "P6") (pin "2") (pinfunction "2_2") (pintype "passive"))
    )
    (net (code "43") (name "/LPSPI0_PCS0") (class "Default")
      (node (ref "P6") (pin "6") (pinfunction "6_6") (pintype "passive"))
    )
    (net (code "44") (name "/LPSPI0_PCS2") (class "Default")
      (node (ref "P6") (pin "7") (pinfunction "7_7") (pintype "passive"))
    )
    (net (code "45") (name "/LPSPI0_PCS3") (class "Default")
      (node (ref "P6") (pin "8") (pinfunction "8_8") (pintype "passive"))
    )
    (net (code "46") (name "/LPSPI0_SCK") (class "Default")
      (node (ref "P6") (pin "10") (pinfunction "10_10") (pintype "passive"))
    )
    (net (code "47") (name "/LPSPI1_MISO") (class "Default")
      (node (ref "U1") (pin "25") (pinfunction "MISO_25") (pintype "passive"))
    )
    (net (code "48") (name "/LPSPI1_MOSI") (class "Default")
      (node (ref "U1") (pin "26") (pinfunction "MOSI_26") (pintype "passive"))
    )
    (net (code "49") (name "/LPSPI1_PCS0") (class "Default")
      (node (ref "P6") (pin "5") (pinfunction "5_5") (pintype "passive"))
    )
    (net (code "50") (name "/LPSPI1_PCS2") (class "Default")
      (node (ref "U1") (pin "28") (pinfunction "CS_28") (pintype "passive"))
    )
    (net (code "51") (name "/LPSPI1_PCS3") (class "Default")
      (node (ref "P6") (pin "9") (pinfunction "9_9") (pintype "passive"))
    )
    (net (code "52") (name "/LPSPI1_SCK") (class "Default")
      (node (ref "U1") (pin "27") (pinfunction "SCLK_27") (pintype "passive"))
    )
    (net (code "53") (name "/LPUART2_RX") (class "Default")
      (node (ref "R12") (pin "2") (pinfunction "2_2") (pintype "passive"))
    )
    (net (code "54") (name "/LPUART2_R_RX") (class "Default")
      (node (ref "R12") (pin "1") (pinfunction "1_1") (pintype "passive"))
      (node (ref "U1") (pin "23") (pinfunction "RXDL_23") (pintype "passive"))
    )
    (net (code "55") (name "/LPUART2_R_TX") (class "Default")
      (node (ref "R13") (pin "1") (pinfunction "1_1") (pintype "passive"))
      (node (ref "U1") (pin "22") (pinfunction "TXDL_22") (pintype "passive"))
    )
    (net (code "56") (name "/LPUART2_TX") (class "Default")
      (node (ref "R13") (pin "2") (pinfunction "2_2") (pintype "passive"))
    )
    (net (code "57") (name "/N$40") (class "Default")
      (node (ref "P5") (pin "7") (pinfunction "7_7") (pintype "passive"))
    )
    (net (code "58") (name "/N$41") (class "Default")
      (node (ref "P5") (pin "9") (pinfunction "9_9") (pintype "passive"))
    )
    (net (code "59") (name "/NMI_B") (class "Default")
      (node (ref "C18") (pin "1") (pinfunction "1_1") (pintype "passive"))
      (node (ref "U1") (pin "29") (pinfunction "INT_29") (pintype "passive"))
    )
    (net (code "60") (name "/RESET_B") (class "Default")
      (node (ref "C19") (pin "1") (pinfunction "1_1") (pintype "passive"))
      (node (ref "P5") (pin "10") (pinfunction "10_10") (pintype "passive"))
      (node (ref "U1") (pin "24") (pinfunction "RST_24") (pintype "passive"))
    )
    (net (code "61") (name "/SELECT") (class "Default")
      (node (ref "R10") (pin "2") (pinfunction "2_2") (pintype "passive"))
      (node (ref "U1") (pin "31") (pinfunction "SELECT_31") (pintype "passive"))
    )
    (net (code "62") (name "/SPARE2") (class "Default")
      (node (ref "P1") (pin "3") (pinfunction "3_3") (pintype "passive"))
    )
    (net (code "63") (name "/SPARE3") (class "Default")
      (node (ref "P1") (pin "4") (pinfunction "4_4") (pintype "passive"))
    )
    (net (code "64") (name "/SPARE4") (class "Default")
      (node (ref "P1") (pin "5") (pinfunction "5_5") (pintype "passive"))
    )
    (net (code "65") (name "/SPARE5") (class "Default")
      (node (ref "P1") (pin "6") (pinfunction "6_6") (pintype "passive"))
    )
    (net (code "66") (name "/SPARE6") (class "Default")
      (node (ref "P1") (pin "7") (pinfunction "7_7") (pintype "passive"))
    )
    (net (code "67") (name "/SPARE7") (class "Default")
      (node (ref "P1") (pin "8") (pinfunction "8_8") (pintype "passive"))
    )
    (net (code "68") (name "/SPARE8") (class "Default")
      (node (ref "P1") (pin "9") (pinfunction "9_9") (pintype "passive"))
    )
    (net (code "69") (name "/SPARE9") (class "Default")
      (node (ref "P1") (pin "10") (pinfunction "10_10") (pintype "passive"))
    )
    (net (code "70") (name "/SPARE10") (class "Default")
      (node (ref "P1") (pin "11") (pinfunction "11_11") (pintype "passive"))
    )
    (net (code "71") (name "/SPARE11") (class "Default")
      (node (ref "P1") (pin "12") (pinfunction "12_12") (pintype "passive"))
    )
    (net (code "72") (name "/SW_CORE") (class "Default")
      (node (ref "C11") (pin "1") (pinfunction "1_1") (pintype "passive"))
      (node (ref "C14") (pin "2") (pinfunction "2_2") (pintype "passive"))
      (node (ref "D4") (pin "1") (pinfunction "Cathode_1") (pintype "passive"))
      (node (ref "L3") (pin "1") (pinfunction "1_1") (pintype "passive"))
      (node (ref "U1") (pin "35") (pinfunction "SW_CORE_35") (pintype "passive"))
    )
    (net (code "73") (name "/VAUX_B") (class "Default")
      (node (ref "U1") (pin "39") (pinfunction "VAUX_B_39") (pintype "passive"))
    )
    (net (code "74") (name "/VAUX_E") (class "Default")
      (node (ref "U1") (pin "40") (pinfunction "VAUX_E_40") (pintype "passive"))
    )
    (net (code "75") (name "/VCCA_B") (class "Default")
      (node (ref "U1") (pin "42") (pinfunction "VCCA_B_42") (pintype "passive"))
    )
    (net (code "76") (name "/VCCA_E") (class "Default")
      (node (ref "U1") (pin "41") (pinfunction "VCCA_E_41") (pintype "passive"))
    )
    (net (code "77") (name "/Vsense") (class "Default")
      (node (ref "C15") (pin "1") (pinfunction "1_1") (pintype "passive"))
      (node (ref "R3") (pin "2") (pinfunction "2_2") (pintype "passive"))
      (node (ref "U1") (pin "3") (pinfunction "VSENSE_3") (pintype "passive"))
    )
    (net (code "78") (name "GND") (class "Default")
      (node (ref "C10") (pin "2") (pinfunction "2_2") (pintype "passive"))
      (node (ref "C15") (pin "2") (pinfunction "2_2") (pintype "passive"))
      (node (ref "C18") (pin "2") (pinfunction "2_2") (pintype "passive"))
      (node (ref "C19") (pin "2") (pinfunction "2_2") (pintype "passive"))
      (node (ref "C20") (pin "2") (pinfunction "2_2") (pintype "passive"))
      (node (ref "C21") (pin "2") (pinfunction "2_2") (pintype "passive"))
      (node (ref "C22") (pin "2") (pinfunction "2_2") (pintype "passive"))
      (node (ref "C23") (pin "2") (pinfunction "2_2") (pintype "passive"))
      (node (ref "C24") (pin "2") (pinfunction "2_2") (pintype "passive"))
      (node (ref "C4") (pin "2") (pinfunction "2_2") (pintype "passive"))
      (node (ref "C5") (pin "2") (pinfunction "2_2") (pintype "passive"))
      (node (ref "C6") (pin "2") (pinfunction "2_2") (pintype "passive"))
      (node (ref "C8") (pin "2") (pinfunction "2_2") (pintype "passive"))
      (node (ref "DZ1") (pin "2") (pinfunction "2_2") (pintype "passive"))
      (node (ref "DZ2") (pin "2") (pinfunction "2_2") (pintype "passive"))
      (node (ref "DZ3") (pin "A") (pinfunction "1_A") (pintype "passive"))
      (node (ref "DZ4") (pin "A") (pinfunction "1_A") (pintype "passive"))
      (node (ref "P1") (pin "2") (pinfunction "2_2") (pintype "passive"))
      (node (ref "P3") (pin "2") (pinfunction "2_2") (pintype "passive"))
      (node (ref "P5") (pin "3") (pinfunction "3_3") (pintype "passive"))
      (node (ref "P6") (pin "3") (pinfunction "3_3") (pintype "passive"))
      (node (ref "Q2") (pin "2") (pinfunction "S_2") (pintype "passive"))
      (node (ref "Q3") (pin "2") (pinfunction "S_2") (pintype "passive"))
      (node (ref "R10") (pin "1") (pinfunction "1_1") (pintype "passive"))
      (node (ref "R11") (pin "1") (pinfunction "1_1") (pintype "passive"))
      (node (ref "R15") (pin "2") (pinfunction "2_2") (pintype "passive"))
      (node (ref "R21") (pin "1") (pinfunction "1_1") (pintype "passive"))
      (node (ref "R25") (pin "1") (pinfunction "1_1") (pintype "passive"))
      (node (ref "R8") (pin "1") (pinfunction "1_1") (pintype "passive"))
      (node (ref "U1") (pin "16") (pinfunction "AGND_16") (pintype "passive"))
      (node (ref "U1") (pin "6") (pinfunction "GND_COM_6") (pintype "passive"))
      (node (ref "U1") (pin "P$49") (pinfunction "EP_P$49") (pintype "passive"))
      (node (ref "U7") (pin "1") (pinfunction "GND/HSINK_2_1") (pintype "power_in"))
      (node (ref "U7") (pin "10") (pinfunction "GND/HSINK_5_10") (pintype "power_in"))
      (node (ref "U7") (pin "11") (pinfunction "GND/HSINK_6_11") (pintype "power_in"))
      (node (ref "U7") (pin "12") (pinfunction "GND/HSINK_7_12") (pintype "power_in"))
      (node (ref "U7") (pin "19") (pinfunction "GND/HSINK_8_19") (pintype "power_in"))
      (node (ref "U7") (pin "2") (pinfunction "GND/HSINK_3_2") (pintype "power_in"))
      (node (ref "U7") (pin "20") (pinfunction "GND/HSINK_20") (pintype "power_in"))
      (node (ref "U7") (pin "3") (pinfunction "GND_3") (pintype "power_in"))
      (node (ref "U7") (pin "9") (pinfunction "GND/HSINK_4_9") (pintype "power_in"))
      (node (ref "U7") (pin "EPAD") (pinfunction "EPAD_EPAD") (pintype "passive"))
    )
    (net (code "79") (name "Net-(C1-Pad2)") (class "Default")
      (node (ref "C1") (pin "2") (pinfunction "2_2") (pintype "passive"))
      (node (ref "R1") (pin "2") (pinfunction "2_2") (pintype "passive"))
    )
    (net (code "80") (name "Net-(C11-Pad2)") (class "Default")
      (node (ref "C11") (pin "2") (pinfunction "2_2") (pintype "passive"))
      (node (ref "R4") (pin "2") (pinfunction "2_2") (pintype "passive"))
    )
    (net (code "81") (name "Net-(C16-Pad1)") (class "Default")
      (node (ref "C16") (pin "1") (pinfunction "1_1") (pintype "passive"))
      (node (ref "R2") (pin "1") (pinfunction "1_1") (pintype "passive"))
    )
    (net (code "82") (name "Net-(C17-Pad2)") (class "Default")
      (node (ref "C17") (pin "2") (pinfunction "2_2") (pintype "passive"))
      (node (ref "R7") (pin "1") (pinfunction "1_1") (pintype "passive"))
    )
    (net (code "83") (name "Net-(D1-Anode)") (class "Default")
      (node (ref "D1") (pin "2") (pinfunction "Anode_2") (pintype "passive"))
      (node (ref "L1") (pin "2") (pinfunction "2_2") (pintype "passive"))
      (node (ref "Q1") (pin "2") (pinfunction "D_2") (pintype "passive"))
      (node (ref "Q1") (pin "4") (pinfunction "4_4") (pintype "passive"))
    )
    (net (code "84") (name "Net-(D2-Cathode)") (class "Default")
      (node (ref "C1") (pin "1") (pinfunction "1_1") (pintype "passive"))
      (node (ref "C9") (pin "1") (pinfunction "1_1") (pintype "passive"))
      (node (ref "D2") (pin "1") (pinfunction "Cathode_1") (pintype "passive"))
      (node (ref "L1") (pin "1") (pinfunction "1_1") (pintype "passive"))
      (node (ref "U1") (pin "47") (pinfunction "SW_PRE2_47") (pintype "passive"))
      (node (ref "U1") (pin "48") (pinfunction "SW_PRE1_48") (pintype "passive"))
    )
    (net (code "85") (name "Net-(D5-Anode)") (class "Default")
      (node (ref "D5") (pin "2") (pinfunction "Anode_2") (pintype "passive"))
      (node (ref "R5") (pin "1") (pinfunction "1_1") (pintype "passive"))
    )
    (net (code "86") (name "Net-(U1-BOOT_CORE)") (class "Default")
      (node (ref "C14") (pin "1") (pinfunction "1_1") (pintype "passive"))
      (node (ref "U1") (pin "36") (pinfunction "BOOT_CORE_36") (pintype "passive"))
    )
    (net (code "87") (name "Net-(U1-BOOT_PRE)") (class "Default")
      (node (ref "C9") (pin "2") (pinfunction "2_2") (pintype "passive"))
      (node (ref "U1") (pin "46") (pinfunction "BOOT_PRE_46") (pintype "passive"))
    )
    (net (code "88") (name "Net-(U1-DEBUG)") (class "Default")
      (node (ref "Tp2") (pin "1") (pinfunction "1_1") (pintype "passive"))
      (node (ref "U1") (pin "15") (pinfunction "DEBUG_15") (pintype "passive"))
    )
    (net (code "89") (name "Net-(U1-IO_2)") (class "Default")
      (node (ref "Tp4") (pin "1") (pinfunction "1_1") (pintype "passive"))
      (node (ref "U1") (pin "18") (pinfunction "IO_2_18") (pintype "passive"))
    )
    (net (code "90") (name "Net-(U1-IO_3)") (class "Default")
      (node (ref "Tp3") (pin "1") (pinfunction "1_1") (pintype "passive"))
      (node (ref "U1") (pin "19") (pinfunction "IO_3_19") (pintype "passive"))
    )
    (net (code "91") (name "Net-(U1-IO_4)") (class "Default")
      (node (ref "Tp1") (pin "1") (pinfunction "1_1") (pintype "passive"))
      (node (ref "U1") (pin "10") (pinfunction "IO_4_10") (pintype "passive"))
    )
    (net (code "92") (name "Net-(U7-FB{slash}NC)") (class "Default")
      (node (ref "R15") (pin "1") (pinfunction "1_1") (pintype "passive"))
      (node (ref "R18") (pin "2") (pinfunction "2_2") (pintype "passive"))
      (node (ref "U7") (pin "15") (pinfunction "FB/NC_15") (pintype "passive"))
    )
    (net (code "93") (name "Net-(U7-PG)") (class "Default")
      (node (ref "R17") (pin "1") (pinfunction "1_1") (pintype "passive"))
      (node (ref "U7") (pin "16") (pinfunction "PG_16") (pintype "passive"))
    )
    (net (code "94") (name "PGND") (class "Default")
      (node (ref "C12") (pin "2") (pinfunction "2_2") (pintype "passive"))
      (node (ref "C13") (pin "2") (pinfunction "2_2") (pintype "passive"))
      (node (ref "C2") (pin "2") (pinfunction "2_2") (pintype "passive"))
      (node (ref "C3") (pin "2") (pinfunction "2_2") (pintype "passive"))
      (node (ref "C7") (pin "2") (pinfunction "2_2") (pintype "passive"))
      (node (ref "D2") (pin "2") (pinfunction "Anode_2") (pintype "passive"))
      (node (ref "D4") (pin "2") (pinfunction "Anode_2") (pintype "passive"))
      (node (ref "Q1") (pin "3") (pinfunction "S_3") (pintype "passive"))
      (node (ref "R1") (pin "1") (pinfunction "1_1") (pintype "passive"))
      (node (ref "R4") (pin "1") (pinfunction "1_1") (pintype "passive"))
      (node (ref "U1") (pin "45") (pinfunction "DGND_45") (pintype "passive"))
    )
    (net (code "95") (name "unconnected-(P5-Pad5)") (class "Default")
      (node (ref "P5") (pin "5") (pinfunction "5_5") (pintype "passive"))
    )
    (net (code "96") (name "unconnected-(U7-NC-Pad18)") (class "Default")
      (node (ref "U7") (pin "18") (pinfunction "NC_18") (pintype "passive"))
    )
    (net (code "97") (name "unconnected-(U7-NC_2-Pad4)") (class "Default")
      (node (ref "U7") (pin "4") (pinfunction "NC_2_4") (pintype "passive"))
    )
    (net (code "98") (name "unconnected-(U7-NC_3-Pad8)") (class "Default")
      (node (ref "U7") (pin "8") (pinfunction "NC_3_8") (pintype "passive"))
    )
    (net (code "99") (name "unconnected-(U7-NC_4-Pad17)") (class "Default")
      (node (ref "U7") (pin "17") (pinfunction "NC_4_17") (pintype "passive"))
    )
  )
)
